# rf_lpf_80.net
KiCad netlist of a schematic drawn in Altium Designer
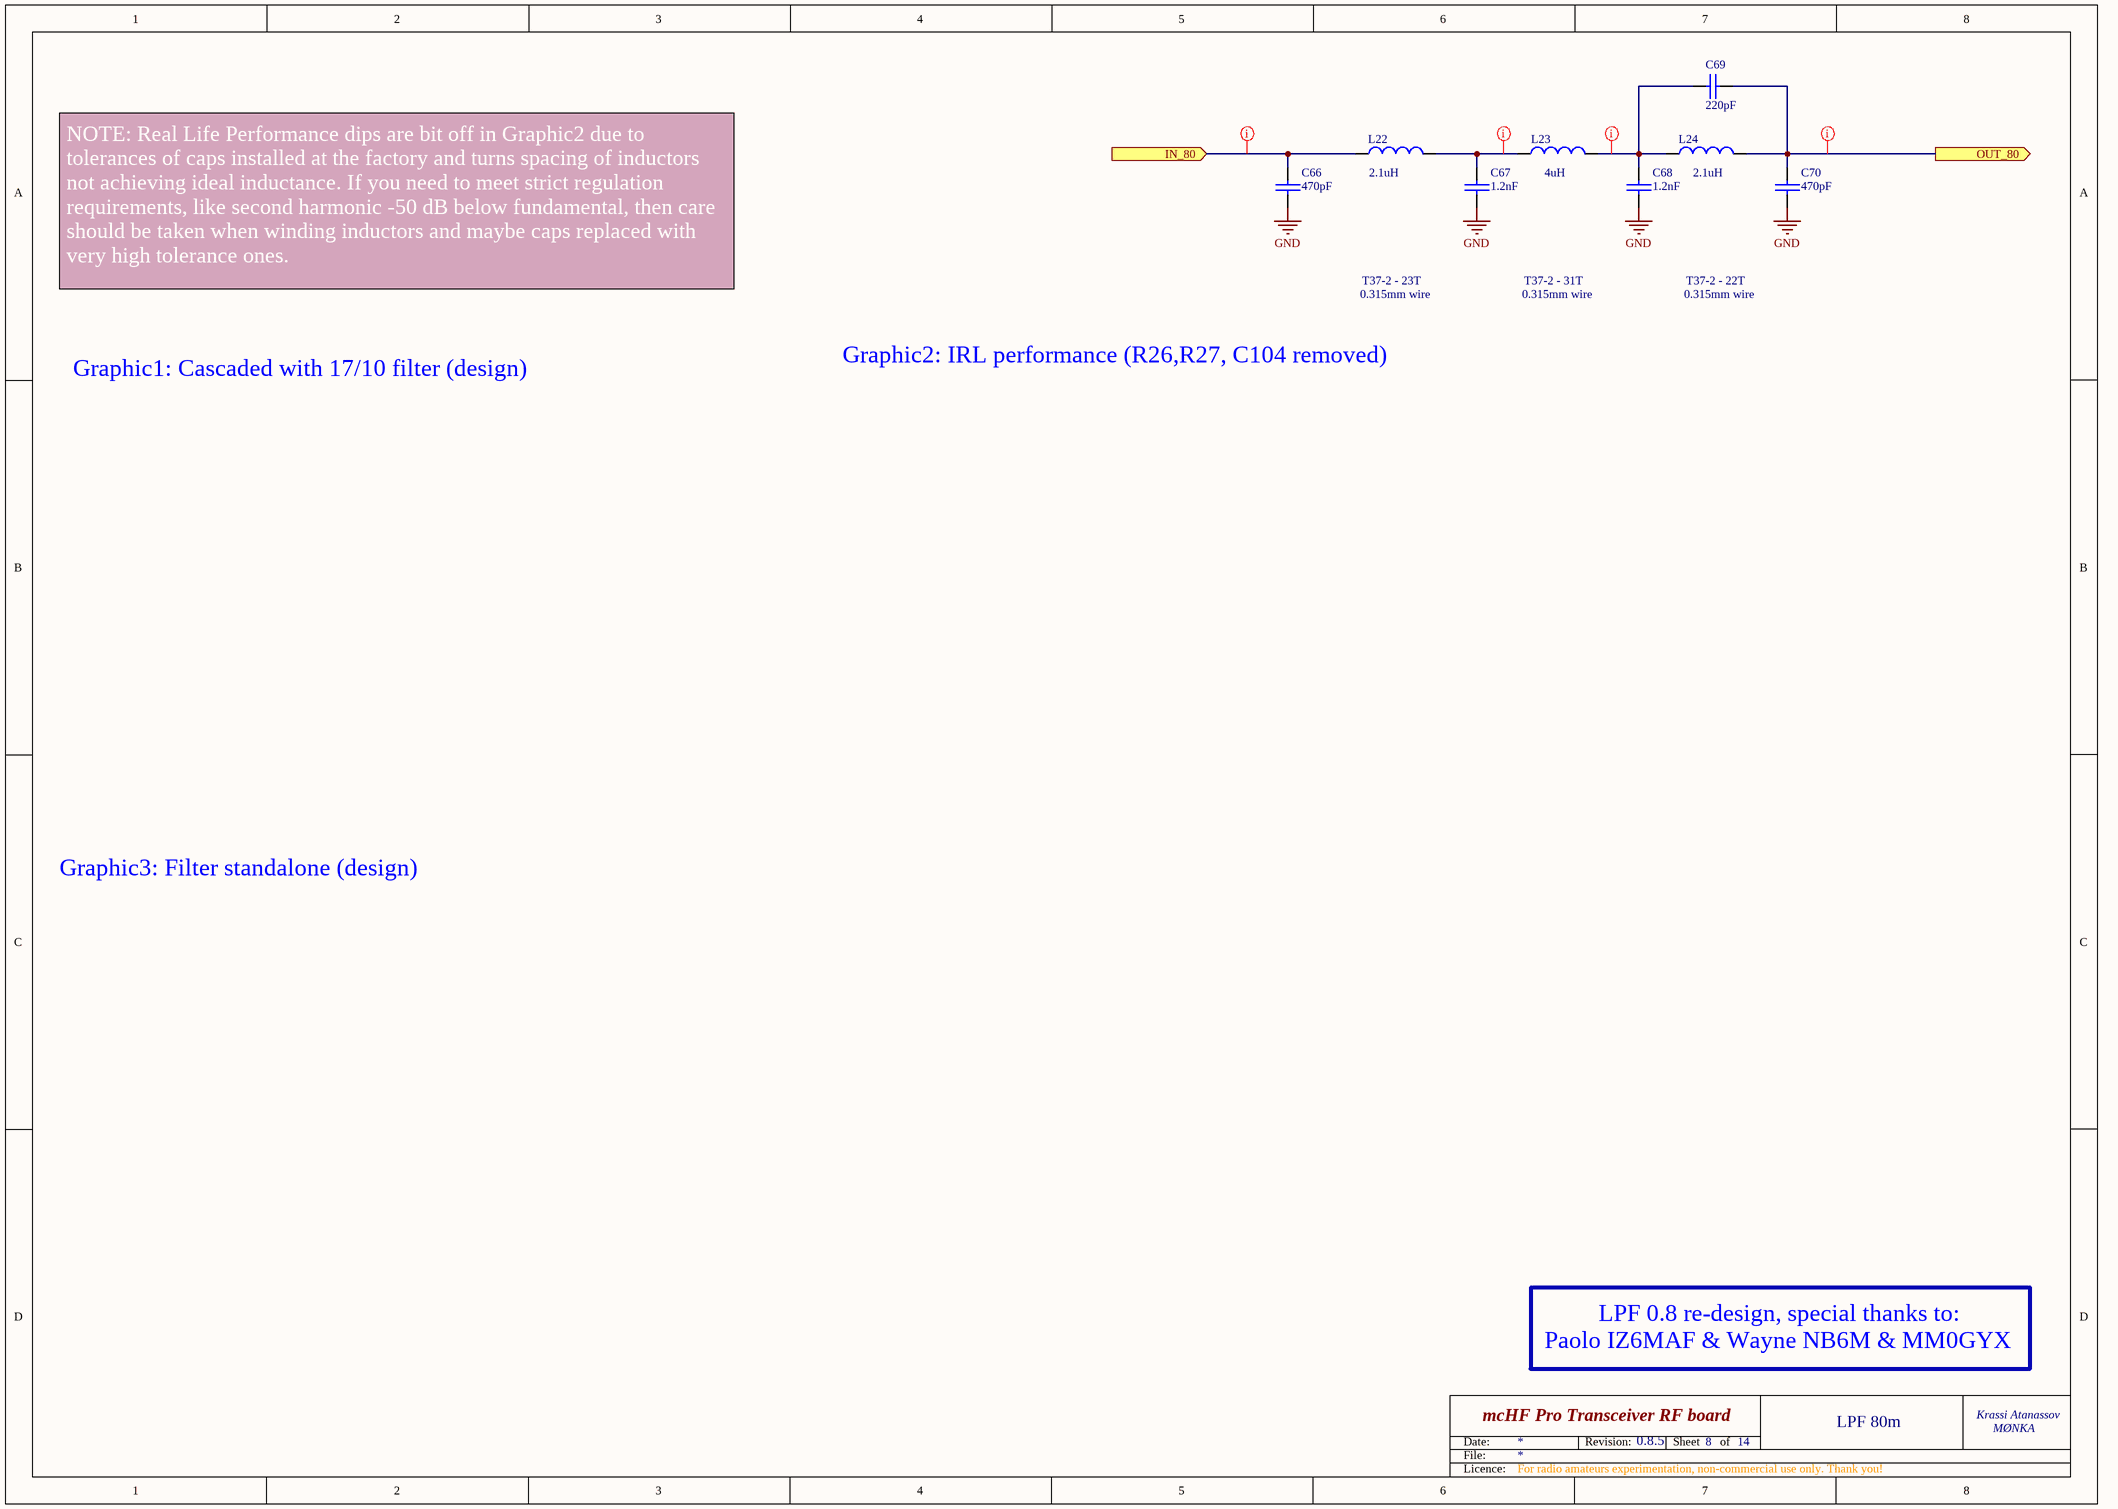
[diagram p0: rf_lpf_80.SchDoc]

(export (version "E")
  (design (tool "Eeschema 10.0.6"))
  (components
    (comp (ref "C66")
      (value "470pF")
      (footprint "0805")
      (description "Capacitor")
      (fields (field (name "VOLTAGE") "100V"))
      (libsource (lib "mcHF_rf") (part "CAP"))
    )
    (comp (ref "C67")
      (value "1.2nF")
      (footprint "0805")
      (description "Capacitor")
      (fields (field (name "VOLTAGE") "100V"))
      (libsource (lib "mcHF_rf") (part "CAP"))
    )
    (comp (ref "C68")
      (value "1.2nF")
      (footprint "0805")
      (description "Capacitor")
      (fields (field (name "VOLTAGE") "100V"))
      (libsource (lib "mcHF_rf") (part "CAP"))
    )
    (comp (ref "C69")
      (value "220pF")
      (footprint "0805")
      (description "Capacitor")
      (fields (field (name "VOLTAGE") "100V"))
      (libsource (lib "mcHF_rf") (part "CAP"))
    )
    (comp (ref "C70")
      (value "470pF")
      (footprint "0805")
      (description "Capacitor")
      (fields (field (name "VOLTAGE") "100V"))
      (libsource (lib "mcHF_rf") (part "CAP"))
    )
    (comp (ref "L22")
      (value "T37-2")
      (footprint "LPF_IND")
      (description "T37-2 handwound inductor")
      (fields (field (name "INDUCTANCE") "2.1uH"))
      (libsource (lib "mcHF_rf") (part "LPF_IND"))
    )
    (comp (ref "L23")
      (value "T37-2")
      (footprint "LPF_IND")
      (description "T37-2 handwound inductor")
      (fields (field (name "INDUCTANCE") "4uH"))
      (libsource (lib "mcHF_rf") (part "LPF_IND"))
    )
    (comp (ref "L24")
      (value "T37-2")
      (footprint "LPF_IND")
      (description "T37-2 handwound inductor")
      (fields (field (name "INDUCTANCE") "2.1uH"))
      (libsource (lib "mcHF_rf") (part "LPF_IND"))
    )
  )
  (nets
    (net (code "1") (name "/IN_80") (class "Default")
      (node (ref "C66") (pin "1") (pinfunction "1_1") (pintype "passive"))
      (node (ref "L22") (pin "1") (pinfunction "1_1") (pintype "passive"))
    )
    (net (code "2") (name "/OUT_80") (class "Default")
      (node (ref "C69") (pin "1") (pinfunction "1_1") (pintype "passive"))
      (node (ref "C70") (pin "1") (pinfunction "1_1") (pintype "passive"))
      (node (ref "L24") (pin "2") (pinfunction "2_2") (pintype "passive"))
    )
    (net (code "3") (name "GND") (class "Default")
      (node (ref "C66") (pin "2") (pinfunction "2_2") (pintype "passive"))
      (node (ref "C67") (pin "2") (pinfunction "2_2") (pintype "passive"))
      (node (ref "C68") (pin "2") (pinfunction "2_2") (pintype "passive"))
      (node (ref "C70") (pin "2") (pinfunction "2_2") (pintype "passive"))
    )
    (net (code "4") (name "Net-(C67-Pad1)") (class "Default")
      (node (ref "C67") (pin "1") (pinfunction "1_1") (pintype "passive"))
      (node (ref "L22") (pin "2") (pinfunction "2_2") (pintype "passive"))
      (node (ref "L23") (pin "1") (pinfunction "1_1") (pintype "passive"))
    )
    (net (code "5") (name "Net-(C68-Pad1)") (class "Default")
      (node (ref "C68") (pin "1") (pinfunction "1_1") (pintype "passive"))
      (node (ref "C69") (pin "2") (pinfunction "2_2") (pintype "passive"))
      (node (ref "L23") (pin "2") (pinfunction "2_2") (pintype "passive"))
      (node (ref "L24") (pin "1") (pinfunction "1_1") (pintype "passive"))
    )
  )
)
